# HDMI_switch.net
KiCad netlist of a schematic drawn in EasyEDA
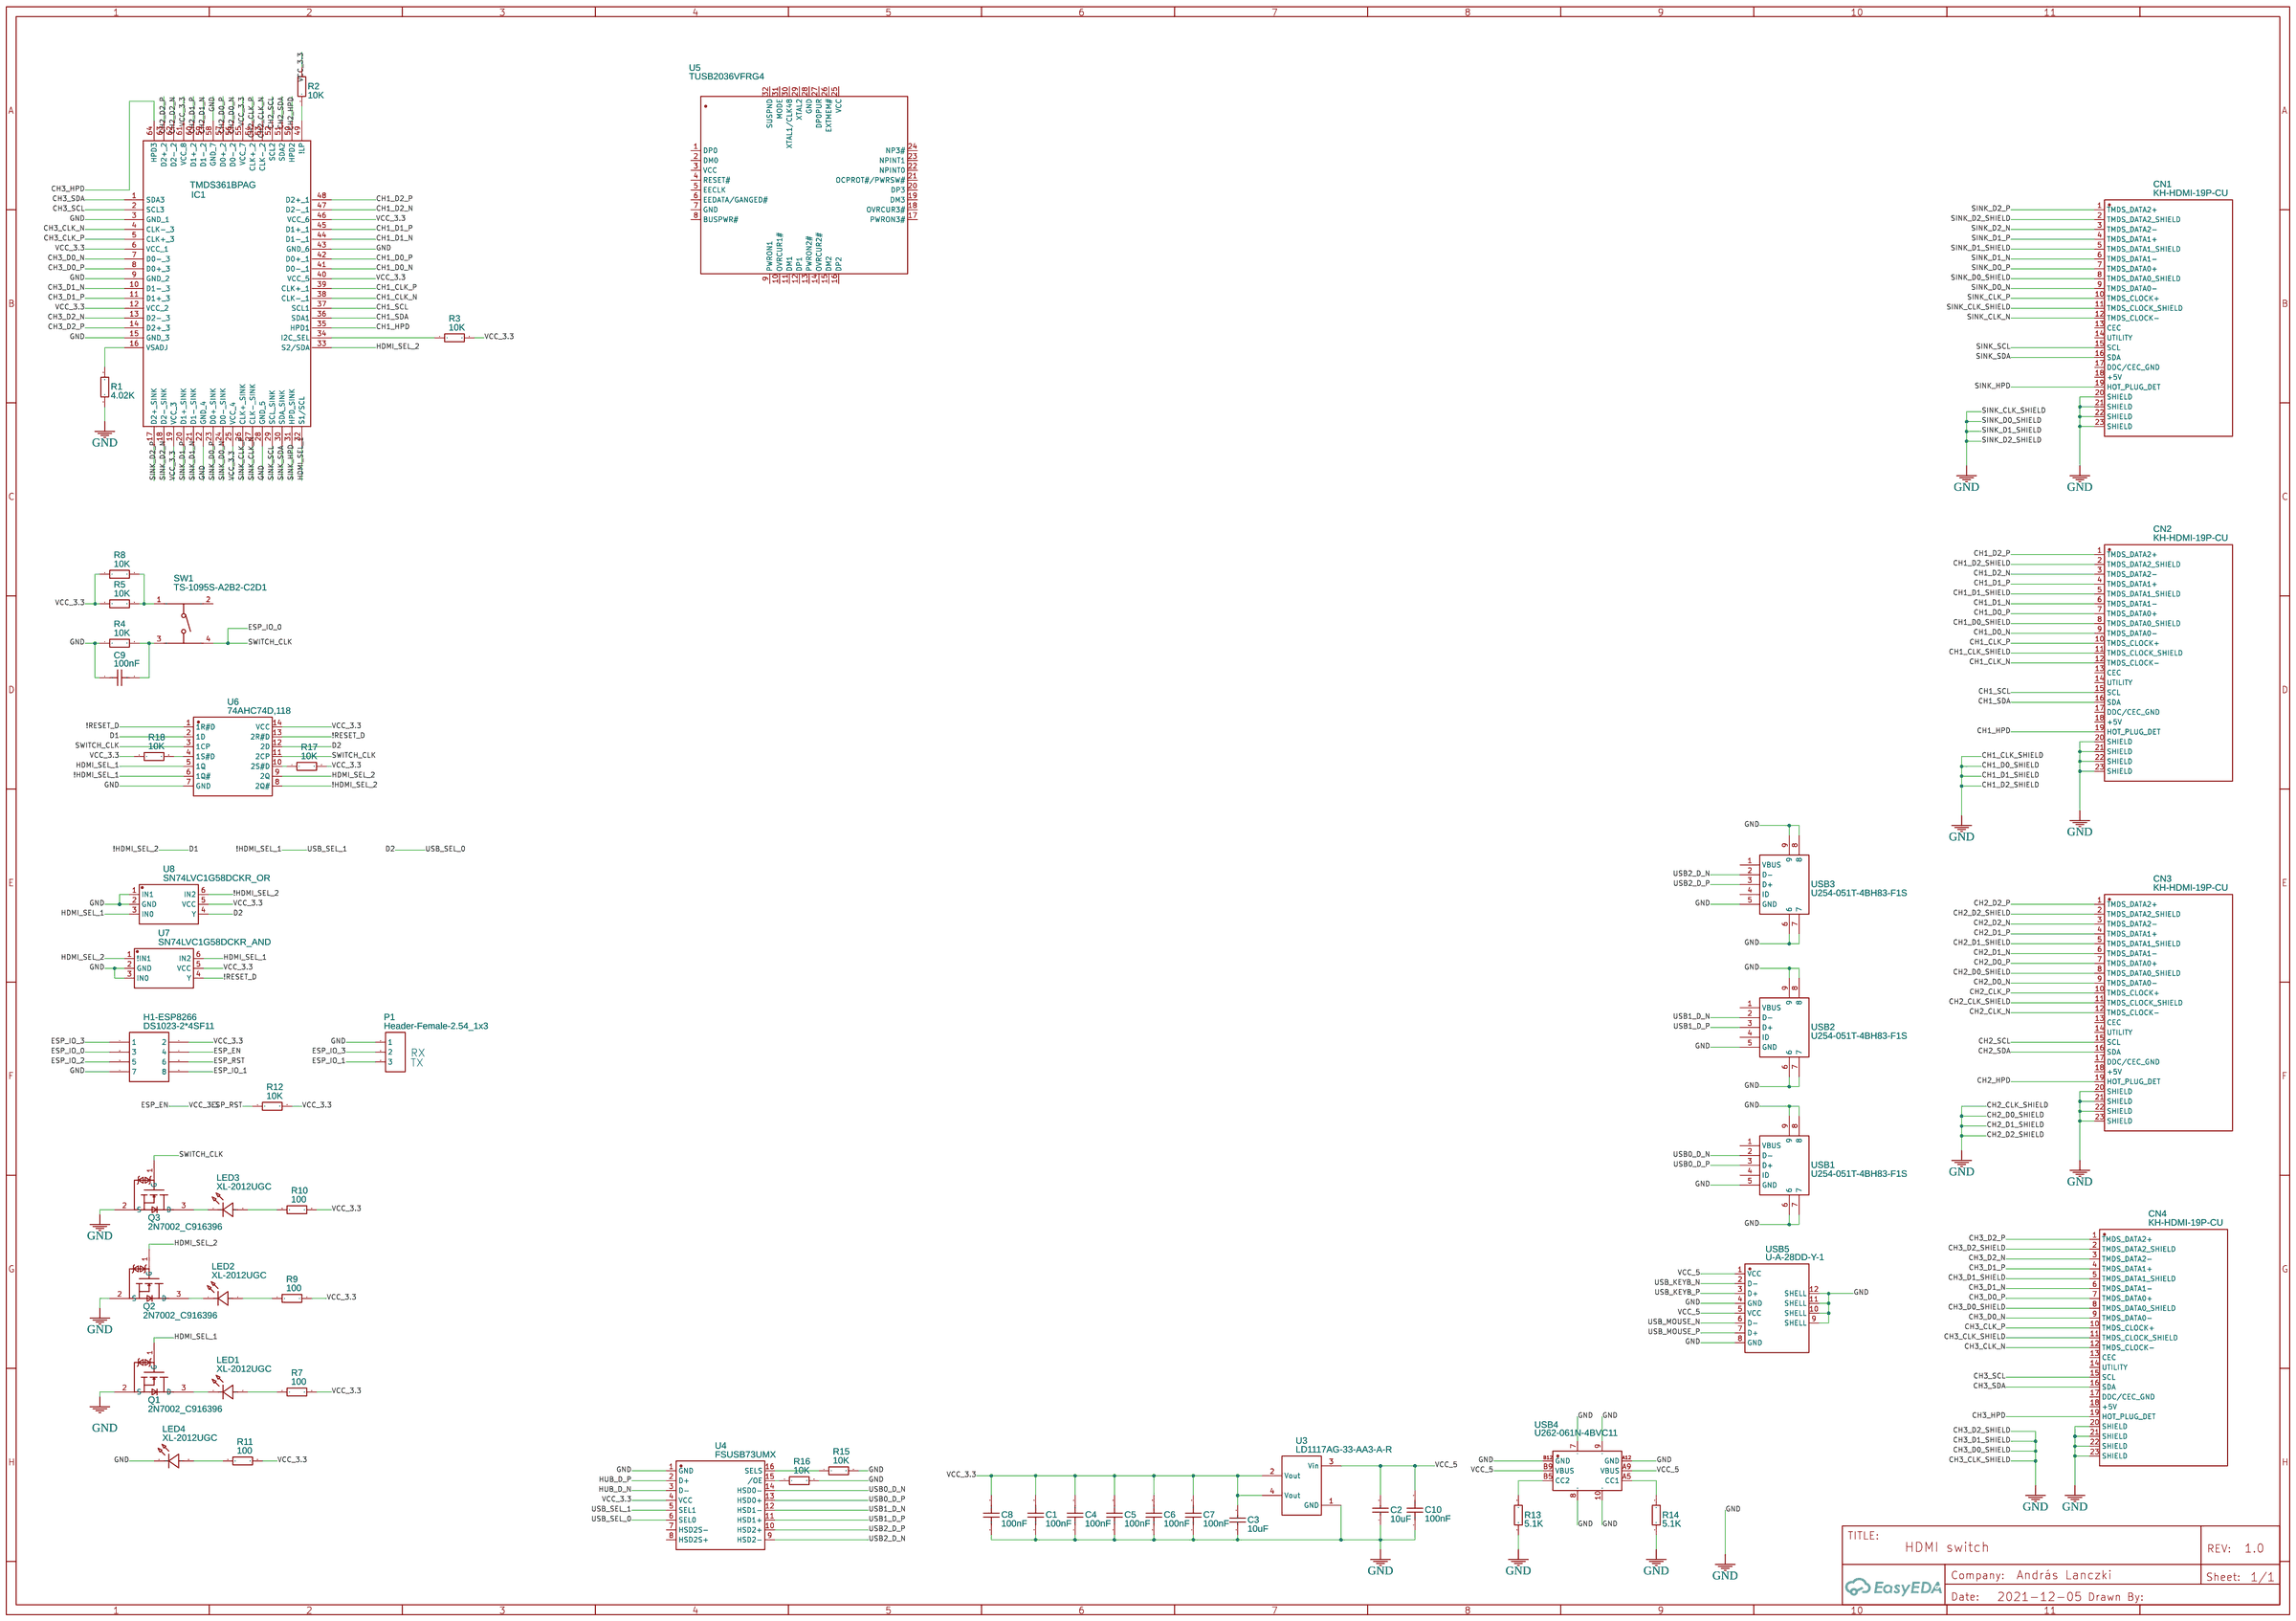
[diagram p0: schematic sheet]

(export (version "E")
  (design (tool "Eeschema 10.0.6"))
  (components
    (comp (ref "C1")
      (value "100nF")
      (fields
        (field (name "BOM_Manufacturer Part") "CC0402KRX7R7BB104")
        (field (name "BOM_Supplier Part") "C60474")
      )
      (libsource (lib "") (part "CC0402KRX7R7BB104"))
    )
    (comp (ref "C2")
      (value "10uF")
      (fields
        (field (name "BOM_Manufacturer Part") "CL31A106KAHNNNE")
        (field (name "BOM_Supplier Part") "C9807")
      )
      (libsource (lib "") (part "CL31A106KAHNNNE"))
    )
    (comp (ref "C3")
      (value "10uF")
      (fields
        (field (name "BOM_Manufacturer Part") "CL31A106KAHNNNE")
        (field (name "BOM_Supplier Part") "C9807")
      )
      (libsource (lib "") (part "CL31A106KAHNNNE"))
    )
    (comp (ref "C4")
      (value "100nF")
      (fields
        (field (name "BOM_Manufacturer Part") "CC0402KRX7R7BB104")
        (field (name "BOM_Supplier Part") "C60474")
      )
      (libsource (lib "") (part "CC0402KRX7R7BB104"))
    )
    (comp (ref "C5")
      (value "100nF")
      (fields
        (field (name "BOM_Manufacturer Part") "CC0402KRX7R7BB104")
        (field (name "BOM_Supplier Part") "C60474")
      )
      (libsource (lib "") (part "CC0402KRX7R7BB104"))
    )
    (comp (ref "C6")
      (value "100nF")
      (fields
        (field (name "BOM_Manufacturer Part") "CC0402KRX7R7BB104")
        (field (name "BOM_Supplier Part") "C60474")
      )
      (libsource (lib "") (part "CC0402KRX7R7BB104"))
    )
    (comp (ref "C7")
      (value "100nF")
      (fields
        (field (name "BOM_Manufacturer Part") "CC0402KRX7R7BB104")
        (field (name "BOM_Supplier Part") "C60474")
      )
      (libsource (lib "") (part "CC0402KRX7R7BB104"))
    )
    (comp (ref "C8")
      (value "100nF")
      (fields
        (field (name "BOM_Manufacturer Part") "CC0402KRX7R7BB104")
        (field (name "BOM_Supplier Part") "C60474")
      )
      (libsource (lib "") (part "CC0402KRX7R7BB104"))
    )
    (comp (ref "C9")
      (value "100nF")
      (fields
        (field (name "BOM_Manufacturer Part") "CC0402KRX7R7BB104")
        (field (name "BOM_Supplier Part") "C60474")
      )
      (libsource (lib "") (part "CC0402KRX7R7BB104_1"))
    )
    (comp (ref "C10")
      (value "100nF")
      (fields
        (field (name "BOM_Manufacturer Part") "CC0402KRX7R7BB104")
        (field (name "BOM_Supplier Part") "C60474")
      )
      (libsource (lib "") (part "CC0402KRX7R7BB104"))
    )
    (comp (ref "CN1")
      (value "KH-HDMI-19P-CU")
      (fields
        (field (name "BOM_Manufacturer Part") "KH-HDMI-19P-Cu")
        (field (name "BOM_Supplier Part") "C709361")
      )
      (libsource (lib "") (part "KH-HDMI-19P-CU"))
    )
    (comp (ref "CN2")
      (value "KH-HDMI-19P-CU")
      (fields
        (field (name "BOM_Manufacturer Part") "KH-HDMI-19P-Cu")
        (field (name "BOM_Supplier Part") "C709361")
      )
      (libsource (lib "") (part "KH-HDMI-19P-CU"))
    )
    (comp (ref "CN3")
      (value "KH-HDMI-19P-CU")
      (fields
        (field (name "BOM_Manufacturer Part") "KH-HDMI-19P-Cu")
        (field (name "BOM_Supplier Part") "C709361")
      )
      (libsource (lib "") (part "KH-HDMI-19P-CU"))
    )
    (comp (ref "CN4")
      (value "KH-HDMI-19P-CU")
      (fields
        (field (name "BOM_Manufacturer Part") "KH-HDMI-19P-Cu")
        (field (name "BOM_Supplier Part") "C709361")
      )
      (libsource (lib "") (part "KH-HDMI-19P-CU"))
    )
    (comp (ref "H1-ESP8266")
      (value "DS1023-2*4SF11")
      (fields (field (name "BOM_Supplier Part") "C92271"))
      (libsource (lib "") (part "DS1023-2*4SF11"))
    )
    (comp (ref "IC1") (value "TMDS361BPAG") (libsource (lib "") (part "TMDS361BPAG")))
    (comp (ref "LED1")
      (value "XL-2012UGC")
      (fields (field (name "BOM_Supplier Part") "C965815"))
      (libsource (lib "") (part "XL-2012UGC"))
    )
    (comp (ref "LED2")
      (value "XL-2012UGC")
      (fields (field (name "BOM_Supplier Part") "C965815"))
      (libsource (lib "") (part "XL-2012UGC"))
    )
    (comp (ref "LED3")
      (value "XL-2012UGC")
      (fields (field (name "BOM_Supplier Part") "C965815"))
      (libsource (lib "") (part "XL-2012UGC"))
    )
    (comp (ref "LED4")
      (value "XL-2012UGC")
      (fields (field (name "BOM_Supplier Part") "C965815"))
      (libsource (lib "") (part "XL-2012UGC"))
    )
    (comp (ref "P1")
      (value "Header-Female-2.54_1x3")
      (fields (field (name "BOM_Supplier Part") "C146243"))
      (libsource (lib "") (part "Header-Female-2.54_1x3"))
    )
    (comp (ref "Q1")
      (value "2N7002_C916396")
      (fields (field (name "BOM_Manufacturer Part") "2N7002") (field (name "BOM_Supplier Part") "C916396"))
      (libsource (lib "") (part "2N7002_C916396"))
    )
    (comp (ref "Q2")
      (value "2N7002_C916396")
      (fields (field (name "BOM_Manufacturer Part") "2N7002") (field (name "BOM_Supplier Part") "C916396"))
      (libsource (lib "") (part "2N7002_C916396"))
    )
    (comp (ref "Q3")
      (value "2N7002_C916396")
      (fields (field (name "BOM_Manufacturer Part") "2N7002") (field (name "BOM_Supplier Part") "C916396"))
      (libsource (lib "") (part "2N7002_C916396"))
    )
    (comp (ref "R1")
      (value "4.02K")
      (fields
        (field (name "BOM_Manufacturer Part") "TC0525B4021T5E")
        (field (name "BOM_Supplier Part") "C88431")
      )
      (libsource (lib "") (part "TC0525B4021T5E"))
    )
    (comp (ref "R2")
      (value "10K")
      (fields
        (field (name "BOM_Manufacturer Part") "RS-03K103JT")
        (field (name "BOM_Supplier Part") "C73809")
      )
      (libsource (lib "") (part "RS-03K103JT_1"))
    )
    (comp (ref "R3")
      (value "10K")
      (fields
        (field (name "BOM_Manufacturer Part") "RS-03K103JT")
        (field (name "BOM_Supplier Part") "C73809")
      )
      (libsource (lib "") (part "RS-03K103JT"))
    )
    (comp (ref "R4")
      (value "10K")
      (fields
        (field (name "BOM_Manufacturer Part") "RS-03K103JT")
        (field (name "BOM_Supplier Part") "C73809")
      )
      (libsource (lib "") (part "RS-03K103JT"))
    )
    (comp (ref "R5")
      (value "10K")
      (fields
        (field (name "BOM_Manufacturer Part") "RS-03K103JT")
        (field (name "BOM_Supplier Part") "C73809")
      )
      (libsource (lib "") (part "RS-03K103JT"))
    )
    (comp (ref "R7")
      (value "100")
      (fields
        (field (name "BOM_Manufacturer Part") "0603WAJ0101T5E")
        (field (name "BOM_Supplier Part") "C25201")
      )
      (libsource (lib "") (part "0603WAJ0101T5E"))
    )
    (comp (ref "R8")
      (value "10K")
      (fields
        (field (name "BOM_Manufacturer Part") "RS-03K103JT")
        (field (name "BOM_Supplier Part") "C73809")
      )
      (libsource (lib "") (part "RS-03K103JT"))
    )
    (comp (ref "R9")
      (value "100")
      (fields
        (field (name "BOM_Manufacturer Part") "0603WAJ0101T5E")
        (field (name "BOM_Supplier Part") "C25201")
      )
      (libsource (lib "") (part "0603WAJ0101T5E"))
    )
    (comp (ref "R10")
      (value "100")
      (fields
        (field (name "BOM_Manufacturer Part") "0603WAJ0101T5E")
        (field (name "BOM_Supplier Part") "C25201")
      )
      (libsource (lib "") (part "0603WAJ0101T5E"))
    )
    (comp (ref "R11")
      (value "100")
      (fields
        (field (name "BOM_Manufacturer Part") "0603WAJ0101T5E")
        (field (name "BOM_Supplier Part") "C25201")
      )
      (libsource (lib "") (part "0603WAJ0101T5E"))
    )
    (comp (ref "R12")
      (value "10K")
      (fields
        (field (name "BOM_Manufacturer Part") "RS-03K103JT")
        (field (name "BOM_Supplier Part") "C73809")
      )
      (libsource (lib "") (part "RS-03K103JT"))
    )
    (comp (ref "R13")
      (value "5.1K")
      (fields
        (field (name "BOM_Manufacturer Part") "RC0402FR-075K1L")
        (field (name "BOM_Supplier Part") "C105872")
      )
      (libsource (lib "") (part "RC0402FR-075K1L"))
    )
    (comp (ref "R14")
      (value "5.1K")
      (fields
        (field (name "BOM_Manufacturer Part") "RC0402FR-075K1L")
        (field (name "BOM_Supplier Part") "C105872")
      )
      (libsource (lib "") (part "RC0402FR-075K1L"))
    )
    (comp (ref "R15")
      (value "10K")
      (fields
        (field (name "BOM_Manufacturer Part") "RS-03K103JT")
        (field (name "BOM_Supplier Part") "C73809")
      )
      (libsource (lib "") (part "RS-03K103JT"))
    )
    (comp (ref "R16")
      (value "10K")
      (fields
        (field (name "BOM_Manufacturer Part") "RS-03K103JT")
        (field (name "BOM_Supplier Part") "C73809")
      )
      (libsource (lib "") (part "RS-03K103JT"))
    )
    (comp (ref "R17")
      (value "10K")
      (fields
        (field (name "BOM_Manufacturer Part") "RS-03K103JT")
        (field (name "BOM_Supplier Part") "C73809")
      )
      (libsource (lib "") (part "RS-03K103JT"))
    )
    (comp (ref "R18")
      (value "10K")
      (fields
        (field (name "BOM_Manufacturer Part") "RS-03K103JT")
        (field (name "BOM_Supplier Part") "C73809")
      )
      (libsource (lib "") (part "RS-03K103JT"))
    )
    (comp (ref "SW1")
      (value "TS-1095S-A2B2-C2D1")
      (fields (field (name "BOM_Supplier Part") "C782826"))
      (libsource (lib "") (part "TS-1095S-A2B2-C2D1"))
    )
    (comp (ref "U3")
      (value "LD1117AG-33-AA3-A-R")
      (fields (field (name "BOM_Supplier Part") "C71121"))
      (libsource (lib "") (part "LD1117AG-33-AA3-A-R"))
    )
    (comp (ref "U4")
      (value "FSUSB73UMX")
      (fields (field (name "BOM_Supplier Part") "C895431"))
      (libsource (lib "") (part "FSUSB73UMX"))
    )
    (comp (ref "U5")
      (value "TUSB2036VFRG4")
      (fields (field (name "BOM_Supplier Part") "C2678093"))
      (libsource (lib "") (part "TUSB2036VFRG4"))
    )
    (comp (ref "U6")
      (value "74AHC74D,118")
      (fields (field (name "BOM_Supplier Part") "C282412"))
      (libsource (lib "") (part "74AHC74D,118"))
    )
    (comp (ref "U7")
      (value "SN74LVC1G58DCKR_AND")
      (fields
        (field (name "BOM_Manufacturer Part") "SN74LVC1G58DCKR")
        (field (name "BOM_Supplier Part") "C7842")
      )
      (libsource (lib "") (part "SN74LVC1G58DCKR"))
    )
    (comp (ref "U8")
      (value "SN74LVC1G58DCKR_OR")
      (fields
        (field (name "BOM_Manufacturer Part") "SN74LVC1G58DCKR")
        (field (name "BOM_Supplier Part") "C7842")
      )
      (libsource (lib "") (part "SN74LVC1G58DCKR_1"))
    )
    (comp (ref "USB1")
      (value "U254-051T-4BH83-F1S")
      (fields (field (name "BOM_Supplier Part") "C397452"))
      (libsource (lib "") (part "U254-051T-4BH83-F1S"))
    )
    (comp (ref "USB2")
      (value "U254-051T-4BH83-F1S")
      (fields (field (name "BOM_Supplier Part") "C397452"))
      (libsource (lib "") (part "U254-051T-4BH83-F1S"))
    )
    (comp (ref "USB3")
      (value "U254-051T-4BH83-F1S")
      (fields (field (name "BOM_Supplier Part") "C397452"))
      (libsource (lib "") (part "U254-051T-4BH83-F1S"))
    )
    (comp (ref "USB4")
      (value "U262-061N-4BVC11")
      (fields (field (name "BOM_Supplier Part") "C2764612"))
      (libsource (lib "") (part "U262-061N-4BVC11"))
    )
    (comp (ref "USB5")
      (value "U-A-28DD-Y-1")
      (fields (field (name "BOM_Supplier Part") "C530601"))
      (libsource (lib "") (part "U-A-28DD-Y-1"))
    )
  )
  (nets
    (net (code "1") (name "/!HDMI_SEL_1") (class "Default")
      (node (ref "U4") (pin "5") (pinfunction "SEL1_5") (pintype "unspecified"))
      (node (ref "U6") (pin "6") (pinfunction "1Q#_6") (pintype "unspecified"))
    )
    (net (code "2") (name "/!HDMI_SEL_2") (class "Default")
      (node (ref "U6") (pin "2") (pinfunction "1D_2") (pintype "unspecified"))
      (node (ref "U6") (pin "8") (pinfunction "2Q#_8") (pintype "unspecified"))
      (node (ref "U8") (pin "6") (pinfunction "IN2_6") (pintype "unspecified"))
    )
    (net (code "3") (name "/!RESET_D") (class "Default")
      (node (ref "U6") (pin "1") (pinfunction "1R#D_1") (pintype "unspecified"))
      (node (ref "U6") (pin "13") (pinfunction "2R#D_13") (pintype "unspecified"))
      (node (ref "U7") (pin "4") (pinfunction "Y_4") (pintype "unspecified"))
    )
    (net (code "4") (name "/CH1_CLK_N") (class "Default")
      (node (ref "CN2") (pin "12") (pinfunction "TMDS_CLOCK-_12") (pintype "unspecified"))
      (node (ref "IC1") (pin "38") (pinfunction "CLK-_1_38") (pintype "bidirectional"))
    )
    (net (code "5") (name "/CH1_CLK_P") (class "Default")
      (node (ref "CN2") (pin "10") (pinfunction "TMDS_CLOCK+_10") (pintype "unspecified"))
      (node (ref "IC1") (pin "39") (pinfunction "CLK+_1_39") (pintype "bidirectional"))
    )
    (net (code "6") (name "/CH1_D0_N") (class "Default")
      (node (ref "CN2") (pin "9") (pinfunction "TMDS_DATA0-_9") (pintype "unspecified"))
      (node (ref "IC1") (pin "41") (pinfunction "D0-_1_41") (pintype "bidirectional"))
    )
    (net (code "7") (name "/CH1_D0_P") (class "Default")
      (node (ref "CN2") (pin "7") (pinfunction "TMDS_DATA0+_7") (pintype "unspecified"))
      (node (ref "IC1") (pin "42") (pinfunction "D0+_1_42") (pintype "bidirectional"))
    )
    (net (code "8") (name "/CH1_D1_N") (class "Default")
      (node (ref "CN2") (pin "6") (pinfunction "TMDS_DATA1-_6") (pintype "unspecified"))
      (node (ref "IC1") (pin "44") (pinfunction "D1-_1_44") (pintype "bidirectional"))
    )
    (net (code "9") (name "/CH1_D1_P") (class "Default")
      (node (ref "CN2") (pin "4") (pinfunction "TMDS_DATA1+_4") (pintype "unspecified"))
      (node (ref "IC1") (pin "45") (pinfunction "D1+_1_45") (pintype "bidirectional"))
    )
    (net (code "10") (name "/CH1_D2_N") (class "Default")
      (node (ref "CN2") (pin "3") (pinfunction "TMDS_DATA2-_3") (pintype "unspecified"))
      (node (ref "IC1") (pin "47") (pinfunction "D2-_1_47") (pintype "bidirectional"))
    )
    (net (code "11") (name "/CH1_D2_P") (class "Default")
      (node (ref "CN2") (pin "1") (pinfunction "TMDS_DATA2+_1") (pintype "unspecified"))
      (node (ref "IC1") (pin "48") (pinfunction "D2+_1_48") (pintype "bidirectional"))
    )
    (net (code "12") (name "/CH1_HPD") (class "Default")
      (node (ref "CN2") (pin "19") (pinfunction "HOT_PLUG_DET_19") (pintype "unspecified"))
      (node (ref "IC1") (pin "35") (pinfunction "HPD1_35") (pintype "bidirectional"))
    )
    (net (code "13") (name "/CH1_SCL") (class "Default")
      (node (ref "CN2") (pin "15") (pinfunction "SCL_15") (pintype "unspecified"))
      (node (ref "IC1") (pin "37") (pinfunction "SCL1_37") (pintype "bidirectional"))
    )
    (net (code "14") (name "/CH1_SDA") (class "Default")
      (node (ref "CN2") (pin "16") (pinfunction "SDA_16") (pintype "unspecified"))
      (node (ref "IC1") (pin "36") (pinfunction "SDA1_36") (pintype "bidirectional"))
    )
    (net (code "15") (name "/CH2_CLK_N") (class "Default")
      (node (ref "CN3") (pin "12") (pinfunction "TMDS_CLOCK-_12") (pintype "unspecified"))
      (node (ref "IC1") (pin "53") (pinfunction "CLK-_2_53") (pintype "bidirectional"))
    )
    (net (code "16") (name "/CH2_CLK_P") (class "Default")
      (node (ref "CN3") (pin "10") (pinfunction "TMDS_CLOCK+_10") (pintype "unspecified"))
      (node (ref "IC1") (pin "54") (pinfunction "CLK+_2_54") (pintype "bidirectional"))
    )
    (net (code "17") (name "/CH2_D0_N") (class "Default")
      (node (ref "CN3") (pin "9") (pinfunction "TMDS_DATA0-_9") (pintype "unspecified"))
      (node (ref "IC1") (pin "56") (pinfunction "D0-_2_56") (pintype "bidirectional"))
    )
    (net (code "18") (name "/CH2_D0_P") (class "Default")
      (node (ref "CN3") (pin "7") (pinfunction "TMDS_DATA0+_7") (pintype "unspecified"))
      (node (ref "IC1") (pin "57") (pinfunction "D0+_2_57") (pintype "bidirectional"))
    )
    (net (code "19") (name "/CH2_D1_N") (class "Default")
      (node (ref "CN3") (pin "6") (pinfunction "TMDS_DATA1-_6") (pintype "unspecified"))
      (node (ref "IC1") (pin "59") (pinfunction "D1-_2_59") (pintype "bidirectional"))
    )
    (net (code "20") (name "/CH2_D1_P") (class "Default")
      (node (ref "CN3") (pin "4") (pinfunction "TMDS_DATA1+_4") (pintype "unspecified"))
      (node (ref "IC1") (pin "60") (pinfunction "D1+_2_60") (pintype "bidirectional"))
    )
    (net (code "21") (name "/CH2_D2_N") (class "Default")
      (node (ref "CN3") (pin "3") (pinfunction "TMDS_DATA2-_3") (pintype "unspecified"))
      (node (ref "IC1") (pin "62") (pinfunction "D2-_2_62") (pintype "bidirectional"))
    )
    (net (code "22") (name "/CH2_D2_P") (class "Default")
      (node (ref "CN3") (pin "1") (pinfunction "TMDS_DATA2+_1") (pintype "unspecified"))
      (node (ref "IC1") (pin "63") (pinfunction "D2+_2_63") (pintype "bidirectional"))
    )
    (net (code "23") (name "/CH2_HPD") (class "Default")
      (node (ref "CN3") (pin "19") (pinfunction "HOT_PLUG_DET_19") (pintype "unspecified"))
      (node (ref "IC1") (pin "50") (pinfunction "HPD2_50") (pintype "bidirectional"))
    )
    (net (code "24") (name "/CH2_SCL") (class "Default")
      (node (ref "CN3") (pin "15") (pinfunction "SCL_15") (pintype "unspecified"))
      (node (ref "IC1") (pin "52") (pinfunction "SCL2_52") (pintype "bidirectional"))
    )
    (net (code "25") (name "/CH2_SDA") (class "Default")
      (node (ref "CN3") (pin "16") (pinfunction "SDA_16") (pintype "unspecified"))
      (node (ref "IC1") (pin "51") (pinfunction "SDA2_51") (pintype "bidirectional"))
    )
    (net (code "26") (name "/CH3_CLK_N") (class "Default")
      (node (ref "CN4") (pin "12") (pinfunction "TMDS_CLOCK-_12") (pintype "unspecified"))
      (node (ref "IC1") (pin "4") (pinfunction "CLK-_3_4") (pintype "bidirectional"))
    )
    (net (code "27") (name "/CH3_CLK_P") (class "Default")
      (node (ref "CN4") (pin "10") (pinfunction "TMDS_CLOCK+_10") (pintype "unspecified"))
      (node (ref "IC1") (pin "5") (pinfunction "CLK+_3_5") (pintype "bidirectional"))
    )
    (net (code "28") (name "/CH3_D0_N") (class "Default")
      (node (ref "CN4") (pin "9") (pinfunction "TMDS_DATA0-_9") (pintype "unspecified"))
      (node (ref "IC1") (pin "7") (pinfunction "D0-_3_7") (pintype "bidirectional"))
    )
    (net (code "29") (name "/CH3_D0_P") (class "Default")
      (node (ref "CN4") (pin "7") (pinfunction "TMDS_DATA0+_7") (pintype "unspecified"))
      (node (ref "IC1") (pin "8") (pinfunction "D0+_3_8") (pintype "bidirectional"))
    )
    (net (code "30") (name "/CH3_D1_N") (class "Default")
      (node (ref "CN4") (pin "6") (pinfunction "TMDS_DATA1-_6") (pintype "unspecified"))
      (node (ref "IC1") (pin "10") (pinfunction "D1-_3_10") (pintype "bidirectional"))
    )
    (net (code "31") (name "/CH3_D1_P") (class "Default")
      (node (ref "CN4") (pin "4") (pinfunction "TMDS_DATA1+_4") (pintype "unspecified"))
      (node (ref "IC1") (pin "11") (pinfunction "D1+_3_11") (pintype "bidirectional"))
    )
    (net (code "32") (name "/CH3_D2_N") (class "Default")
      (node (ref "CN4") (pin "3") (pinfunction "TMDS_DATA2-_3") (pintype "unspecified"))
      (node (ref "IC1") (pin "13") (pinfunction "D2-_3_13") (pintype "bidirectional"))
    )
    (net (code "33") (name "/CH3_D2_P") (class "Default")
      (node (ref "CN4") (pin "1") (pinfunction "TMDS_DATA2+_1") (pintype "unspecified"))
      (node (ref "IC1") (pin "14") (pinfunction "D2+_3_14") (pintype "bidirectional"))
    )
    (net (code "34") (name "/CH3_HPD") (class "Default")
      (node (ref "CN4") (pin "19") (pinfunction "HOT_PLUG_DET_19") (pintype "unspecified"))
      (node (ref "IC1") (pin "64") (pinfunction "HPD3_64") (pintype "bidirectional"))
    )
    (net (code "35") (name "/CH3_SCL") (class "Default")
      (node (ref "CN4") (pin "15") (pinfunction "SCL_15") (pintype "unspecified"))
      (node (ref "IC1") (pin "2") (pinfunction "SCL3_2") (pintype "bidirectional"))
    )
    (net (code "36") (name "/CH3_SDA") (class "Default")
      (node (ref "CN4") (pin "16") (pinfunction "SDA_16") (pintype "unspecified"))
      (node (ref "IC1") (pin "1") (pinfunction "SDA3_1") (pintype "bidirectional"))
    )
    (net (code "37") (name "/D2") (class "Default")
      (node (ref "U4") (pin "6") (pinfunction "SEL0_6") (pintype "unspecified"))
      (node (ref "U6") (pin "12") (pinfunction "2D_12") (pintype "unspecified"))
      (node (ref "U8") (pin "4") (pinfunction "Y_4") (pintype "unspecified"))
    )
    (net (code "38") (name "/ESP_EN") (class "Default")
      (node (ref "C1") (pin "2") (pinfunction "2_2") (pintype "unspecified"))
      (node (ref "C3") (pin "2") (pinfunction "2_2") (pintype "input"))
      (node (ref "C4") (pin "2") (pinfunction "2_2") (pintype "unspecified"))
      (node (ref "C5") (pin "2") (pinfunction "2_2") (pintype "unspecified"))
      (node (ref "C6") (pin "2") (pinfunction "2_2") (pintype "unspecified"))
      (node (ref "C7") (pin "2") (pinfunction "2_2") (pintype "unspecified"))
      (node (ref "C8") (pin "2") (pinfunction "2_2") (pintype "unspecified"))
      (node (ref "H1-ESP8266") (pin "2") (pinfunction "2_2") (pintype "input"))
      (node (ref "H1-ESP8266") (pin "4") (pinfunction "4_4") (pintype "input"))
      (node (ref "IC1") (pin "12") (pinfunction "VCC_2_12") (pintype "bidirectional"))
      (node (ref "IC1") (pin "19") (pinfunction "VCC_3_19") (pintype "bidirectional"))
      (node (ref "IC1") (pin "25") (pinfunction "VCC_4_25") (pintype "bidirectional"))
      (node (ref "IC1") (pin "40") (pinfunction "VCC_5_40") (pintype "bidirectional"))
      (node (ref "IC1") (pin "46") (pinfunction "VCC_6_46") (pintype "bidirectional"))
      (node (ref "IC1") (pin "55") (pinfunction "VCC_7_55") (pintype "bidirectional"))
      (node (ref "IC1") (pin "6") (pinfunction "VCC_1_6") (pintype "bidirectional"))
      (node (ref "IC1") (pin "61") (pinfunction "VCC_8_61") (pintype "bidirectional"))
      (node (ref "R10") (pin "2") (pinfunction "2_2") (pintype "input"))
      (node (ref "R11") (pin "2") (pinfunction "2_2") (pintype "input"))
      (node (ref "R12") (pin "2") (pinfunction "2_2") (pintype "input"))
      (node (ref "R17") (pin "2") (pinfunction "2_2") (pintype "input"))
      (node (ref "R18") (pin "1") (pinfunction "1_1") (pintype "input"))
      (node (ref "R2") (pin "2") (pinfunction "2_2") (pintype "input"))
      (node (ref "R3") (pin "2") (pinfunction "2_2") (pintype "input"))
      (node (ref "R5") (pin "1") (pinfunction "1_1") (pintype "input"))
      (node (ref "R7") (pin "2") (pinfunction "2_2") (pintype "input"))
      (node (ref "R8") (pin "1") (pinfunction "1_1") (pintype "input"))
      (node (ref "R9") (pin "2") (pinfunction "2_2") (pintype "input"))
      (node (ref "U3") (pin "2") (pinfunction "Vout_2") (pintype "unspecified"))
      (node (ref "U3") (pin "4") (pinfunction "Vout_4") (pintype "unspecified"))
      (node (ref "U4") (pin "4") (pinfunction "VCC_4") (pintype "unspecified"))
      (node (ref "U6") (pin "14") (pinfunction "VCC_14") (pintype "unspecified"))
      (node (ref "U7") (pin "5") (pinfunction "VCC_5") (pintype "unspecified"))
      (node (ref "U8") (pin "5") (pinfunction "VCC_5") (pintype "unspecified"))
    )
    (net (code "39") (name "/ESP_IO_0") (class "Default")
      (node (ref "H1-ESP8266") (pin "3") (pinfunction "3_3") (pintype "input"))
      (node (ref "Q3") (pin "1") (pinfunction "G_1") (pintype "unspecified"))
      (node (ref "SW1") (pin "4") (pinfunction "4_4") (pintype "unspecified"))
      (node (ref "U6") (pin "11") (pinfunction "2CP_11") (pintype "unspecified"))
      (node (ref "U6") (pin "3") (pinfunction "1CP_3") (pintype "unspecified"))
    )
    (net (code "40") (name "/ESP_IO_1") (class "Default")
      (node (ref "H1-ESP8266") (pin "8") (pinfunction "8_8") (pintype "input"))
      (node (ref "P1") (pin "3") (pinfunction "3_3") (pintype "input"))
    )
    (net (code "41") (name "/ESP_IO_2") (class "Default")
      (node (ref "H1-ESP8266") (pin "5") (pinfunction "5_5") (pintype "input"))
    )
    (net (code "42") (name "/ESP_IO_3") (class "Default")
      (node (ref "H1-ESP8266") (pin "1") (pinfunction "1_1") (pintype "input"))
      (node (ref "P1") (pin "2") (pinfunction "2_2") (pintype "input"))
    )
    (net (code "43") (name "/ESP_RST") (class "Default")
      (node (ref "H1-ESP8266") (pin "6") (pinfunction "6_6") (pintype "input"))
      (node (ref "R12") (pin "1") (pinfunction "1_1") (pintype "input"))
    )
    (net (code "44") (name "/HDMI_SEL_1") (class "Default")
      (node (ref "IC1") (pin "32") (pinfunction "S1/SCL_32") (pintype "bidirectional"))
      (node (ref "Q1") (pin "1") (pinfunction "G_1") (pintype "unspecified"))
      (node (ref "U6") (pin "5") (pinfunction "1Q_5") (pintype "unspecified"))
      (node (ref "U7") (pin "6") (pinfunction "IN2_6") (pintype "unspecified"))
      (node (ref "U8") (pin "3") (pinfunction "IN0_3") (pintype "unspecified"))
    )
    (net (code "45") (name "/HDMI_SEL_2") (class "Default")
      (node (ref "IC1") (pin "33") (pinfunction "S2/SDA_33") (pintype "bidirectional"))
      (node (ref "Q2") (pin "1") (pinfunction "G_1") (pintype "unspecified"))
      (node (ref "U6") (pin "9") (pinfunction "2Q_9") (pintype "unspecified"))
      (node (ref "U7") (pin "1") (pinfunction "!IN1_1") (pintype "unspecified"))
    )
    (net (code "46") (name "/HUB_D_N") (class "Default")
      (node (ref "U4") (pin "3") (pinfunction "D-_3") (pintype "unspecified"))
    )
    (net (code "47") (name "/HUB_D_P") (class "Default")
      (node (ref "U4") (pin "2") (pinfunction "D+_2") (pintype "unspecified"))
    )
    (net (code "48") (name "/SINK_CLK_N") (class "Default")
      (node (ref "CN1") (pin "12") (pinfunction "TMDS_CLOCK-_12") (pintype "unspecified"))
      (node (ref "IC1") (pin "27") (pinfunction "CLK-_SINK_27") (pintype "bidirectional"))
    )
    (net (code "49") (name "/SINK_CLK_P") (class "Default")
      (node (ref "CN1") (pin "10") (pinfunction "TMDS_CLOCK+_10") (pintype "unspecified"))
      (node (ref "IC1") (pin "26") (pinfunction "CLK+_SINK_26") (pintype "bidirectional"))
    )
    (net (code "50") (name "/SINK_D0_N") (class "Default")
      (node (ref "CN1") (pin "9") (pinfunction "TMDS_DATA0-_9") (pintype "unspecified"))
      (node (ref "IC1") (pin "24") (pinfunction "D0-_SINK_24") (pintype "bidirectional"))
    )
    (net (code "51") (name "/SINK_D0_P") (class "Default")
      (node (ref "CN1") (pin "7") (pinfunction "TMDS_DATA0+_7") (pintype "unspecified"))
      (node (ref "IC1") (pin "23") (pinfunction "D0+_SINK_23") (pintype "bidirectional"))
    )
    (net (code "52") (name "/SINK_D1_N") (class "Default")
      (node (ref "CN1") (pin "6") (pinfunction "TMDS_DATA1-_6") (pintype "unspecified"))
      (node (ref "IC1") (pin "21") (pinfunction "D1-_SINK_21") (pintype "bidirectional"))
    )
    (net (code "53") (name "/SINK_D1_P") (class "Default")
      (node (ref "CN1") (pin "4") (pinfunction "TMDS_DATA1+_4") (pintype "unspecified"))
      (node (ref "IC1") (pin "20") (pinfunction "D1+_SINK_20") (pintype "bidirectional"))
    )
    (net (code "54") (name "/SINK_D2_N") (class "Default")
      (node (ref "CN1") (pin "3") (pinfunction "TMDS_DATA2-_3") (pintype "unspecified"))
      (node (ref "IC1") (pin "18") (pinfunction "D2-_SINK_18") (pintype "bidirectional"))
    )
    (net (code "55") (name "/SINK_D2_P") (class "Default")
      (node (ref "CN1") (pin "1") (pinfunction "TMDS_DATA2+_1") (pintype "unspecified"))
      (node (ref "IC1") (pin "17") (pinfunction "D2+_SINK_17") (pintype "bidirectional"))
    )
    (net (code "56") (name "/SINK_HPD") (class "Default")
      (node (ref "CN1") (pin "19") (pinfunction "HOT_PLUG_DET_19") (pintype "unspecified"))
      (node (ref "IC1") (pin "31") (pinfunction "HPD_SINK_31") (pintype "bidirectional"))
    )
    (net (code "57") (name "/SINK_SCL") (class "Default")
      (node (ref "CN1") (pin "15") (pinfunction "SCL_15") (pintype "unspecified"))
      (node (ref "IC1") (pin "29") (pinfunction "SCL_SINK_29") (pintype "bidirectional"))
    )
    (net (code "58") (name "/SINK_SDA") (class "Default")
      (node (ref "CN1") (pin "16") (pinfunction "SDA_16") (pintype "unspecified"))
      (node (ref "IC1") (pin "30") (pinfunction "SDA_SINK_30") (pintype "bidirectional"))
    )
    (net (code "59") (name "/USB0_D_N") (class "Default")
      (node (ref "U4") (pin "14") (pinfunction "HSD0-_14") (pintype "unspecified"))
      (node (ref "USB1") (pin "2") (pinfunction "D-_2") (pintype "unspecified"))
    )
    (net (code "60") (name "/USB0_D_P") (class "Default")
      (node (ref "U4") (pin "13") (pinfunction "HSD0+_13") (pintype "unspecified"))
      (node (ref "USB1") (pin "3") (pinfunction "D+_3") (pintype "unspecified"))
    )
    (net (code "61") (name "/USB1_D_N") (class "Default")
      (node (ref "U4") (pin "12") (pinfunction "HSD1-_12") (pintype "unspecified"))
      (node (ref "USB2") (pin "2") (pinfunction "D-_2") (pintype "unspecified"))
    )
    (net (code "62") (name "/USB1_D_P") (class "Default")
      (node (ref "U4") (pin "11") (pinfunction "HSD1+_11") (pintype "unspecified"))
      (node (ref "USB2") (pin "3") (pinfunction "D+_3") (pintype "unspecified"))
    )
    (net (code "63") (name "/USB2_D_N") (class "Default")
      (node (ref "U4") (pin "9") (pinfunction "HSD2-_9") (pintype "unspecified"))
      (node (ref "USB3") (pin "2") (pinfunction "D-_2") (pintype "unspecified"))
    )
    (net (code "64") (name "/USB2_D_P") (class "Default")
      (node (ref "U4") (pin "10") (pinfunction "HSD2+_10") (pintype "unspecified"))
      (node (ref "USB3") (pin "3") (pinfunction "D+_3") (pintype "unspecified"))
    )
    (net (code "65") (name "/USB_KEYB_N") (class "Default")
      (node (ref "USB5") (pin "2") (pinfunction "D-_2") (pintype "unspecified"))
    )
    (net (code "66") (name "/USB_KEYB_P") (class "Default")
      (node (ref "USB5") (pin "3") (pinfunction "D+_3") (pintype "unspecified"))
    )
    (net (code "67") (name "/USB_MOUSE_N") (class "Default")
      (node (ref "USB5") (pin "6") (pinfunction "D-_6") (pintype "unspecified"))
    )
    (net (code "68") (name "/USB_MOUSE_P") (class "Default")
      (node (ref "USB5") (pin "7") (pinfunction "D+_7") (pintype "unspecified"))
    )
    (net (code "69") (name "/VCC_5") (class "Default")
      (node (ref "C10") (pin "2") (pinfunction "2_2") (pintype "unspecified"))
      (node (ref "C2") (pin "2") (pinfunction "2_2") (pintype "input"))
      (node (ref "U3") (pin "3") (pinfunction "Vin_3") (pintype "unspecified"))
      (node (ref "USB4") (pin "A9") (pinfunction "VBUS_A9") (pintype "unspecified"))
      (node (ref "USB4") (pin "B9") (pinfunction "VBUS_B9") (pintype "unspecified"))
      (node (ref "USB5") (pin "1") (pinfunction "VCC_1") (pintype "unspecified"))
      (node (ref "USB5") (pin "5") (pinfunction "VCC_5") (pintype "unspecified"))
    )
    (net (code "70") (name "GND") (class "Default")
      (node (ref "C1") (pin "1") (pinfunction "1_1") (pintype "unspecified"))
      (node (ref "C10") (pin "1") (pinfunction "1_1") (pintype "unspecified"))
      (node (ref "C2") (pin "1") (pinfunction "1_1") (pintype "input"))
      (node (ref "C3") (pin "1") (pinfunction "1_1") (pintype "input"))
      (node (ref "C4") (pin "1") (pinfunction "1_1") (pintype "unspecified"))
      (node (ref "C5") (pin "1") (pinfunction "1_1") (pintype "unspecified"))
      (node (ref "C6") (pin "1") (pinfunction "1_1") (pintype "unspecified"))
      (node (ref "C7") (pin "1") (pinfunction "1_1") (pintype "unspecified"))
      (node (ref "C8") (pin "1") (pinfunction "1_1") (pintype "unspecified"))
      (node (ref "C9") (pin "1") (pinfunction "1_1") (pintype "unspecified"))
      (node (ref "CN1") (pin "11") (pinfunction "TMDS_CLOCK_SHIELD_11") (pintype "unspecified"))
      (node (ref "CN1") (pin "2") (pinfunction "TMDS_DATA2_SHIELD_2") (pintype "unspecified"))
      (node (ref "CN1") (pin "20") (pinfunction "SHIELD_20") (pintype "unspecified"))
      (node (ref "CN1") (pin "21") (pinfunction "SHIELD_21") (pintype "unspecified"))
      (node (ref "CN1") (pin "22") (pinfunction "SHIELD_22") (pintype "unspecified"))
      (node (ref "CN1") (pin "23") (pinfunction "SHIELD_23") (pintype "unspecified"))
      (node (ref "CN1") (pin "5") (pinfunction "TMDS_DATA1_SHIELD_5") (pintype "unspecified"))
      (node (ref "CN1") (pin "8") (pinfunction "TMDS_DATA0_SHIELD_8") (pintype "unspecified"))
      (node (ref "CN2") (pin "11") (pinfunction "TMDS_CLOCK_SHIELD_11") (pintype "unspecified"))
      (node (ref "CN2") (pin "2") (pinfunction "TMDS_DATA2_SHIELD_2") (pintype "unspecified"))
      (node (ref "CN2") (pin "20") (pinfunction "SHIELD_20") (pintype "unspecified"))
      (node (ref "CN2") (pin "21") (pinfunction "SHIELD_21") (pintype "unspecified"))
      (node (ref "CN2") (pin "22") (pinfunction "SHIELD_22") (pintype "unspecified"))
      (node (ref "CN2") (pin "23") (pinfunction "SHIELD_23") (pintype "unspecified"))
      (node (ref "CN2") (pin "5") (pinfunction "TMDS_DATA1_SHIELD_5") (pintype "unspecified"))
      (node (ref "CN2") (pin "8") (pinfunction "TMDS_DATA0_SHIELD_8") (pintype "unspecified"))
      (node (ref "CN3") (pin "11") (pinfunction "TMDS_CLOCK_SHIELD_11") (pintype "unspecified"))
      (node (ref "CN3") (pin "2") (pinfunction "TMDS_DATA2_SHIELD_2") (pintype "unspecified"))
      (node (ref "CN3") (pin "20") (pinfunction "SHIELD_20") (pintype "unspecified"))
      (node (ref "CN3") (pin "21") (pinfunction "SHIELD_21") (pintype "unspecified"))
      (node (ref "CN3") (pin "22") (pinfunction "SHIELD_22") (pintype "unspecified"))
      (node (ref "CN3") (pin "23") (pinfunction "SHIELD_23") (pintype "unspecified"))
      (node (ref "CN3") (pin "5") (pinfunction "TMDS_DATA1_SHIELD_5") (pintype "unspecified"))
      (node (ref "CN3") (pin "8") (pinfunction "TMDS_DATA0_SHIELD_8") (pintype "unspecified"))
      (node (ref "CN4") (pin "11") (pinfunction "TMDS_CLOCK_SHIELD_11") (pintype "unspecified"))
      (node (ref "CN4") (pin "2") (pinfunction "TMDS_DATA2_SHIELD_2") (pintype "unspecified"))
      (node (ref "CN4") (pin "20") (pinfunction "SHIELD_20") (pintype "unspecified"))
      (node (ref "CN4") (pin "21") (pinfunction "SHIELD_21") (pintype "unspecified"))
      (node (ref "CN4") (pin "22") (pinfunction "SHIELD_22") (pintype "unspecified"))
      (node (ref "CN4") (pin "23") (pinfunction "SHIELD_23") (pintype "unspecified"))
      (node (ref "CN4") (pin "5") (pinfunction "TMDS_DATA1_SHIELD_5") (pintype "unspecified"))
      (node (ref "CN4") (pin "8") (pinfunction "TMDS_DATA0_SHIELD_8") (pintype "unspecified"))
      (node (ref "H1-ESP8266") (pin "7") (pinfunction "7_7") (pintype "input"))
      (node (ref "IC1") (pin "15") (pinfunction "GND_3_15") (pintype "bidirectional"))
      (node (ref "IC1") (pin "22") (pinfunction "GND_4_22") (pintype "bidirectional"))
      (node (ref "IC1") (pin "28") (pinfunction "GND_5_28") (pintype "bidirectional"))
      (node (ref "IC1") (pin "3") (pinfunction "GND_1_3") (pintype "bidirectional"))
      (node (ref "IC1") (pin "43") (pinfunction "GND_6_43") (pintype "bidirectional"))
      (node (ref "IC1") (pin "58") (pinfunction "GND_7_58") (pintype "bidirectional"))
      (node (ref "IC1") (pin "9") (pinfunction "GND_2_9") (pintype "bidirectional"))
      (node (ref "LED4") (pin "1") (pinfunction "K_1") (pintype "unspecified"))
      (node (ref "P1") (pin "1") (pinfunction "1_1") (pintype "input"))
      (node (ref "Q1") (pin "2") (pinfunction "S_2") (pintype "unspecified"))
      (node (ref "Q2") (pin "2") (pinfunction "S_2") (pintype "unspecified"))
      (node (ref "Q3") (pin "2") (pinfunction "S_2") (pintype "unspecified"))
      (node (ref "R1") (pin "1") (pinfunction "1_1") (pintype "input"))
      (node (ref "R13") (pin "1") (pinfunction "1_1") (pintype "input"))
      (node (ref "R14") (pin "1") (pinfunction "1_1") (pintype "input"))
      (node (ref "R15") (pin "2") (pinfunction "2_2") (pintype "input"))
      (node (ref "R16") (pin "2") (pinfunction "2_2") (pintype "input"))
      (node (ref "R4") (pin "1") (pinfunction "1_1") (pintype "input"))
      (node (ref "U3") (pin "1") (pinfunction "GND_1") (pintype "unspecified"))
      (node (ref "U4") (pin "1") (pinfunction "GND_1") (pintype "unspecified"))
      (node (ref "U6") (pin "7") (pinfunction "GND_7") (pintype "unspecified"))
      (node (ref "U7") (pin "2") (pinfunction "GND_2") (pintype "unspecified"))
      (node (ref "U7") (pin "3") (pinfunction "IN0_3") (pintype "unspecified"))
      (node (ref "U8") (pin "1") (pinfunction "IN1_1") (pintype "unspecified"))
      (node (ref "U8") (pin "2") (pinfunction "GND_2") (pintype "unspecified"))
      (node (ref "USB1") (pin "5") (pinfunction "GND_5") (pintype "unspecified"))
      (node (ref "USB1") (pin "6") (pinfunction "6_6") (pintype "unspecified"))
      (node (ref "USB1") (pin "7") (pinfunction "7_7") (pintype "unspecified"))
      (node (ref "USB1") (pin "8") (pinfunction "8_8") (pintype "unspecified"))
      (node (ref "USB1") (pin "9") (pinfunction "9_9") (pintype "unspecified"))
      (node (ref "USB2") (pin "5") (pinfunction "GND_5") (pintype "unspecified"))
      (node (ref "USB2") (pin "6") (pinfunction "6_6") (pintype "unspecified"))
      (node (ref "USB2") (pin "7") (pinfunction "7_7") (pintype "unspecified"))
      (node (ref "USB2") (pin "8") (pinfunction "8_8") (pintype "unspecified"))
      (node (ref "USB2") (pin "9") (pinfunction "9_9") (pintype "unspecified"))
      (node (ref "USB3") (pin "5") (pinfunction "GND_5") (pintype "unspecified"))
      (node (ref "USB3") (pin "6") (pinfunction "6_6") (pintype "unspecified"))
      (node (ref "USB3") (pin "7") (pinfunction "7_7") (pintype "unspecified"))
      (node (ref "USB3") (pin "8") (pinfunction "8_8") (pintype "unspecified"))
      (node (ref "USB3") (pin "9") (pinfunction "9_9") (pintype "unspecified"))
      (node (ref "USB4") (pin "10") (pinfunction "10_10") (pintype "unspecified"))
      (node (ref "USB4") (pin "7") (pinfunction "7_7") (pintype "unspecified"))
      (node (ref "USB4") (pin "8") (pinfunction "8_8") (pintype "unspecified"))
      (node (ref "USB4") (pin "9") (pinfunction "9_9") (pintype "unspecified"))
      (node (ref "USB4") (pin "A12") (pinfunction "GND_A12") (pintype "unspecified"))
      (node (ref "USB4") (pin "B12") (pinfunction "GND_B12") (pintype "unspecified"))
      (node (ref "USB5") (pin "10") (pinfunction "SHELL_10") (pintype "unspecified"))
      (node (ref "USB5") (pin "11") (pinfunction "SHELL_11") (pintype "unspecified"))
      (node (ref "USB5") (pin "12") (pinfunction "SHELL_12") (pintype "unspecified"))
      (node (ref "USB5") (pin "4") (pinfunction "GND_4") (pintype "unspecified"))
      (node (ref "USB5") (pin "8") (pinfunction "GND_8") (pintype "unspecified"))
      (node (ref "USB5") (pin "9") (pinfunction "SHELL_9") (pintype "unspecified"))
    )
    (net (code "71") (name "Net-(C9-Pad2)") (class "Default")
      (node (ref "C9") (pin "2") (pinfunction "2_2") (pintype "unspecified"))
      (node (ref "R4") (pin "2") (pinfunction "2_2") (pintype "input"))
      (node (ref "SW1") (pin "3") (pinfunction "3_3") (pintype "unspecified"))
    )
    (net (code "72") (name "Net-(IC1-!LP)") (class "Default")
      (node (ref "IC1") (pin "49") (pinfunction "!LP_49") (pintype "bidirectional"))
      (node (ref "R2") (pin "1") (pinfunction "1_1") (pintype "input"))
    )
    (net (code "73") (name "Net-(IC1-I2C_SEL)") (class "Default")
      (node (ref "IC1") (pin "34") (pinfunction "I2C_SEL_34") (pintype "bidirectional"))
      (node (ref "R3") (pin "1") (pinfunction "1_1") (pintype "input"))
    )
    (net (code "74") (name "Net-(IC1-VSADJ)") (class "Default")
      (node (ref "IC1") (pin "16") (pinfunction "VSADJ_16") (pintype "bidirectional"))
      (node (ref "R1") (pin "2") (pinfunction "2_2") (pintype "input"))
    )
    (net (code "75") (name "Net-(LED1-A)") (class "Default")
      (node (ref "LED1") (pin "2") (pinfunction "A_2") (pintype "unspecified"))
      (node (ref "R7") (pin "1") (pinfunction "1_1") (pintype "input"))
    )
    (net (code "76") (name "Net-(LED1-K)") (class "Default")
      (node (ref "LED1") (pin "1") (pinfunction "K_1") (pintype "unspecified"))
      (node (ref "Q1") (pin "3") (pinfunction "D_3") (pintype "unspecified"))
    )
    (net (code "77") (name "Net-(LED2-A)") (class "Default")
      (node (ref "LED2") (pin "2") (pinfunction "A_2") (pintype "unspecified"))
      (node (ref "R9") (pin "1") (pinfunction "1_1") (pintype "input"))
    )
    (net (code "78") (name "Net-(LED2-K)") (class "Default")
      (node (ref "LED2") (pin "1") (pinfunction "K_1") (pintype "unspecified"))
      (node (ref "Q2") (pin "3") (pinfunction "D_3") (pintype "unspecified"))
    )
    (net (code "79") (name "Net-(LED3-A)") (class "Default")
      (node (ref "LED3") (pin "2") (pinfunction "A_2") (pintype "unspecified"))
      (node (ref "R10") (pin "1") (pinfunction "1_1") (pintype "input"))
    )
    (net (code "80") (name "Net-(LED3-K)") (class "Default")
      (node (ref "LED3") (pin "1") (pinfunction "K_1") (pintype "unspecified"))
      (node (ref "Q3") (pin "3") (pinfunction "D_3") (pintype "unspecified"))
    )
    (net (code "81") (name "Net-(LED4-A)") (class "Default")
      (node (ref "LED4") (pin "2") (pinfunction "A_2") (pintype "unspecified"))
      (node (ref "R11") (pin "1") (pinfunction "1_1") (pintype "input"))
    )
    (net (code "82") (name "Net-(R5-Pad2)") (class "Default")
      (node (ref "R5") (pin "2") (pinfunction "2_2") (pintype "input"))
      (node (ref "R8") (pin "2") (pinfunction "2_2") (pintype "input"))
      (node (ref "SW1") (pin "1") (pinfunction "1_1") (pintype "unspecified"))
    )
    (net (code "83") (name "Net-(U4-SELS)") (class "Default")
      (node (ref "R15") (pin "1") (pinfunction "1_1") (pintype "input"))
      (node (ref "U4") (pin "16") (pinfunction "SELS_16") (pintype "unspecified"))
    )
    (net (code "84") (name "Net-(U4-{slash}OE)") (class "Default")
      (node (ref "R16") (pin "1") (pinfunction "1_1") (pintype "input"))
      (node (ref "U4") (pin "15") (pinfunction "/OE_15") (pintype "unspecified"))
    )
    (net (code "85") (name "Net-(U6-1S#D)") (class "Default")
      (node (ref "R18") (pin "2") (pinfunction "2_2") (pintype "input"))
      (node (ref "U6") (pin "4") (pinfunction "1S#D_4") (pintype "unspecified"))
    )
    (net (code "86") (name "Net-(U6-2S#D)") (class "Default")
      (node (ref "R17") (pin "1") (pinfunction "1_1") (pintype "input"))
      (node (ref "U6") (pin "10") (pinfunction "2S#D_10") (pintype "unspecified"))
    )
    (net (code "87") (name "Net-(USB4-CC1)") (class "Default")
      (node (ref "R14") (pin "2") (pinfunction "2_2") (pintype "input"))
      (node (ref "USB4") (pin "A5") (pinfunction "CC1_A5") (pintype "unspecified"))
    )
    (net (code "88") (name "Net-(USB4-CC2)") (class "Default")
      (node (ref "R13") (pin "2") (pinfunction "2_2") (pintype "input"))
      (node (ref "USB4") (pin "B5") (pinfunction "CC2_B5") (pintype "unspecified"))
    )
    (net (code "89") (name "unconnected-(CN1-+5V-Pad18)") (class "Default")
      (node (ref "CN1") (pin "18") (pinfunction "+5V_18") (pintype "unspecified"))
    )
    (net (code "90") (name "unconnected-(CN1-CEC-Pad13)") (class "Default")
      (node (ref "CN1") (pin "13") (pinfunction "CEC_13") (pintype "unspecified"))
    )
    (net (code "91") (name "unconnected-(CN1-DDC{slash}CEC_GND-Pad17)") (class "Default")
      (node (ref "CN1") (pin "17") (pinfunction "DDC/CEC_GND_17") (pintype "unspecified"))
    )
    (net (code "92") (name "unconnected-(CN1-UTILITY-Pad14)") (class "Default")
      (node (ref "CN1") (pin "14") (pinfunction "UTILITY_14") (pintype "unspecified"))
    )
    (net (code "93") (name "unconnected-(CN2-+5V-Pad18)") (class "Default")
      (node (ref "CN2") (pin "18") (pinfunction "+5V_18") (pintype "unspecified"))
    )
    (net (code "94") (name "unconnected-(CN2-CEC-Pad13)") (class "Default")
      (node (ref "CN2") (pin "13") (pinfunction "CEC_13") (pintype "unspecified"))
    )
    (net (code "95") (name "unconnected-(CN2-DDC{slash}CEC_GND-Pad17)") (class "Default")
      (node (ref "CN2") (pin "17") (pinfunction "DDC/CEC_GND_17") (pintype "unspecified"))
    )
    (net (code "96") (name "unconnected-(CN2-UTILITY-Pad14)") (class "Default")
      (node (ref "CN2") (pin "14") (pinfunction "UTILITY_14") (pintype "unspecified"))
    )
    (net (code "97") (name "unconnected-(CN3-+5V-Pad18)") (class "Default")
      (node (ref "CN3") (pin "18") (pinfunction "+5V_18") (pintype "unspecified"))
    )
    (net (code "98") (name "unconnected-(CN3-CEC-Pad13)") (class "Default")
      (node (ref "CN3") (pin "13") (pinfunction "CEC_13") (pintype "unspecified"))
    )
    (net (code "99") (name "unconnected-(CN3-DDC{slash}CEC_GND-Pad17)") (class "Default")
      (node (ref "CN3") (pin "17") (pinfunction "DDC/CEC_GND_17") (pintype "unspecified"))
    )
    (net (code "100") (name "unconnected-(CN3-UTILITY-Pad14)") (class "Default")
      (node (ref "CN3") (pin "14") (pinfunction "UTILITY_14") (pintype "unspecified"))
    )
    (net (code "101") (name "unconnected-(CN4-+5V-Pad18)") (class "Default")
      (node (ref "CN4") (pin "18") (pinfunction "+5V_18") (pintype "unspecified"))
    )
    (net (code "102") (name "unconnected-(CN4-CEC-Pad13)") (class "Default")
      (node (ref "CN4") (pin "13") (pinfunction "CEC_13") (pintype "unspecified"))
    )
    (net (code "103") (name "unconnected-(CN4-DDC{slash}CEC_GND-Pad17)") (class "Default")
      (node (ref "CN4") (pin "17") (pinfunction "DDC/CEC_GND_17") (pintype "unspecified"))
    )
    (net (code "104") (name "unconnected-(CN4-UTILITY-Pad14)") (class "Default")
      (node (ref "CN4") (pin "14") (pinfunction "UTILITY_14") (pintype "unspecified"))
    )
    (net (code "105") (name "unconnected-(SW1-Pad2)") (class "Default")
      (node (ref "SW1") (pin "2") (pinfunction "2_2") (pintype "unspecified"))
    )
    (net (code "106") (name "unconnected-(U4-HSD2S+-Pad8)") (class "Default")
      (node (ref "U4") (pin "8") (pinfunction "HSD2S+_8") (pintype "unspecified"))
    )
    (net (code "107") (name "unconnected-(U4-HSD2S--Pad7)") (class "Default")
      (node (ref "U4") (pin "7") (pinfunction "HSD2S-_7") (pintype "unspecified"))
    )
    (net (code "108") (name "unconnected-(U5-BUSPWR#-Pad8)") (class "Default")
      (node (ref "U5") (pin "8") (pinfunction "BUSPWR#_8") (pintype "unspecified"))
    )
    (net (code "109") (name "unconnected-(U5-DM0-Pad2)") (class "Default")
      (node (ref "U5") (pin "2") (pinfunction "DM0_2") (pintype "unspecified"))
    )
    (net (code "110") (name "unconnected-(U5-DM1-Pad11)") (class "Default")
      (node (ref "U5") (pin "11") (pinfunction "DM1_11") (pintype "unspecified"))
    )
    (net (code "111") (name "unconnected-(U5-DM2-Pad15)") (class "Default")
      (node (ref "U5") (pin "15") (pinfunction "DM2_15") (pintype "unspecified"))
    )
    (net (code "112") (name "unconnected-(U5-DM3-Pad19)") (class "Default")
      (node (ref "U5") (pin "19") (pinfunction "DM3_19") (pintype "unspecified"))
    )
    (net (code "113") (name "unconnected-(U5-DP0-Pad1)") (class "Default")
      (node (ref "U5") (pin "1") (pinfunction "DP0_1") (pintype "unspecified"))
    )
    (net (code "114") (name "unconnected-(U5-DP0PUR-Pad27)") (class "Default")
      (node (ref "U5") (pin "27") (pinfunction "DP0PUR_27") (pintype "unspecified"))
    )
    (net (code "115") (name "unconnected-(U5-DP1-Pad12)") (class "Default")
      (node (ref "U5") (pin "12") (pinfunction "DP1_12") (pintype "unspecified"))
    )
    (net (code "116") (name "unconnected-(U5-DP2-Pad16)") (class "Default")
      (node (ref "U5") (pin "16") (pinfunction "DP2_16") (pintype "unspecified"))
    )
    (net (code "117") (name "unconnected-(U5-DP3-Pad20)") (class "Default")
      (node (ref "U5") (pin "20") (pinfunction "DP3_20") (pintype "unspecified"))
    )
    (net (code "118") (name "unconnected-(U5-EECLK-Pad5)") (class "Default")
      (node (ref "U5") (pin "5") (pinfunction "EECLK_5") (pintype "unspecified"))
    )
    (net (code "119") (name "unconnected-(U5-EEDATA{slash}GANGED#-Pad6)") (class "Default")
      (node (ref "U5") (pin "6") (pinfunction "EEDATA/GANGED#_6") (pintype "unspecified"))
    )
    (net (code "120") (name "unconnected-(U5-EXTMEM#-Pad26)") (class "Default")
      (node (ref "U5") (pin "26") (pinfunction "EXTMEM#_26") (pintype "unspecified"))
    )
    (net (code "121") (name "unconnected-(U5-GND-Pad7)") (class "Default")
      (node (ref "U5") (pin "7") (pinfunction "GND_7") (pintype "unspecified"))
    )
    (net (code "122") (name "unconnected-(U5-GND-Pad28)") (class "Default")
      (node (ref "U5") (pin "28") (pinfunction "GND_28") (pintype "unspecified"))
    )
    (net (code "123") (name "unconnected-(U5-MODE-Pad31)") (class "Default")
      (node (ref "U5") (pin "31") (pinfunction "MODE_31") (pintype "unspecified"))
    )
    (net (code "124") (name "unconnected-(U5-NP3#-Pad24)") (class "Default")
      (node (ref "U5") (pin "24") (pinfunction "NP3#_24") (pintype "unspecified"))
    )
    (net (code "125") (name "unconnected-(U5-NPINT0-Pad22)") (class "Default")
      (node (ref "U5") (pin "22") (pinfunction "NPINT0_22") (pintype "unspecified"))
    )
    (net (code "126") (name "unconnected-(U5-NPINT1-Pad23)") (class "Default")
      (node (ref "U5") (pin "23") (pinfunction "NPINT1_23") (pintype "unspecified"))
    )
    (net (code "127") (name "unconnected-(U5-OCPROT#{slash}PWRSW#-Pad21)") (class "Default")
      (node (ref "U5") (pin "21") (pinfunction "OCPROT#/PWRSW#_21") (pintype "unspecified"))
    )
    (net (code "128") (name "unconnected-(U5-OVRCUR1#-Pad10)") (class "Default")
      (node (ref "U5") (pin "10") (pinfunction "OVRCUR1#_10") (pintype "unspecified"))
    )
    (net (code "129") (name "unconnected-(U5-OVRCUR2#-Pad14)") (class "Default")
      (node (ref "U5") (pin "14") (pinfunction "OVRCUR2#_14") (pintype "unspecified"))
    )
    (net (code "130") (name "unconnected-(U5-OVRCUR3#-Pad18)") (class "Default")
      (node (ref "U5") (pin "18") (pinfunction "OVRCUR3#_18") (pintype "unspecified"))
    )
    (net (code "131") (name "unconnected-(U5-PWRON1-Pad9)") (class "Default")
      (node (ref "U5") (pin "9") (pinfunction "PWRON1_9") (pintype "unspecified"))
    )
    (net (code "132") (name "unconnected-(U5-PWRON2#-Pad13)") (class "Default")
      (node (ref "U5") (pin "13") (pinfunction "PWRON2#_13") (pintype "unspecified"))
    )
    (net (code "133") (name "unconnected-(U5-PWRON3#-Pad17)") (class "Default")
      (node (ref "U5") (pin "17") (pinfunction "PWRON3#_17") (pintype "unspecified"))
    )
    (net (code "134") (name "unconnected-(U5-RESET#-Pad4)") (class "Default")
      (node (ref "U5") (pin "4") (pinfunction "RESET#_4") (pintype "unspecified"))
    )
    (net (code "135") (name "unconnected-(U5-SUSPND-Pad32)") (class "Default")
      (node (ref "U5") (pin "32") (pinfunction "SUSPND_32") (pintype "unspecified"))
    )
    (net (code "136") (name "unconnected-(U5-VCC-Pad3)") (class "Default")
      (node (ref "U5") (pin "3") (pinfunction "VCC_3") (pintype "unspecified"))
    )
    (net (code "137") (name "unconnected-(U5-VCC-Pad25)") (class "Default")
      (node (ref "U5") (pin "25") (pinfunction "VCC_25") (pintype "unspecified"))
    )
    (net (code "138") (name "unconnected-(U5-XTAL1{slash}CLK48-Pad30)") (class "Default")
      (node (ref "U5") (pin "30") (pinfunction "XTAL1/CLK48_30") (pintype "unspecified"))
    )
    (net (code "139") (name "unconnected-(U5-XTAL2-Pad29)") (class "Default")
      (node (ref "U5") (pin "29") (pinfunction "XTAL2_29") (pintype "unspecified"))
    )
    (net (code "140") (name "unconnected-(USB1-ID-Pad4)") (class "Default")
      (node (ref "USB1") (pin "4") (pinfunction "ID_4") (pintype "unspecified"))
    )
    (net (code "141") (name "unconnected-(USB1-VBUS-Pad1)") (class "Default")
      (node (ref "USB1") (pin "1") (pinfunction "VBUS_1") (pintype "unspecified"))
    )
    (net (code "142") (name "unconnected-(USB2-ID-Pad4)") (class "Default")
      (node (ref "USB2") (pin "4") (pinfunction "ID_4") (pintype "unspecified"))
    )
    (net (code "143") (name "unconnected-(USB2-VBUS-Pad1)") (class "Default")
      (node (ref "USB2") (pin "1") (pinfunction "VBUS_1") (pintype "unspecified"))
    )
    (net (code "144") (name "unconnected-(USB3-ID-Pad4)") (class "Default")
      (node (ref "USB3") (pin "4") (pinfunction "ID_4") (pintype "unspecified"))
    )
    (net (code "145") (name "unconnected-(USB3-VBUS-Pad1)") (class "Default")
      (node (ref "USB3") (pin "1") (pinfunction "VBUS_1") (pintype "unspecified"))
    )
  )
)
